# PAGE03_POWER_SUPPLY.net
KiCad netlist of a schematic drawn in Altium Designer
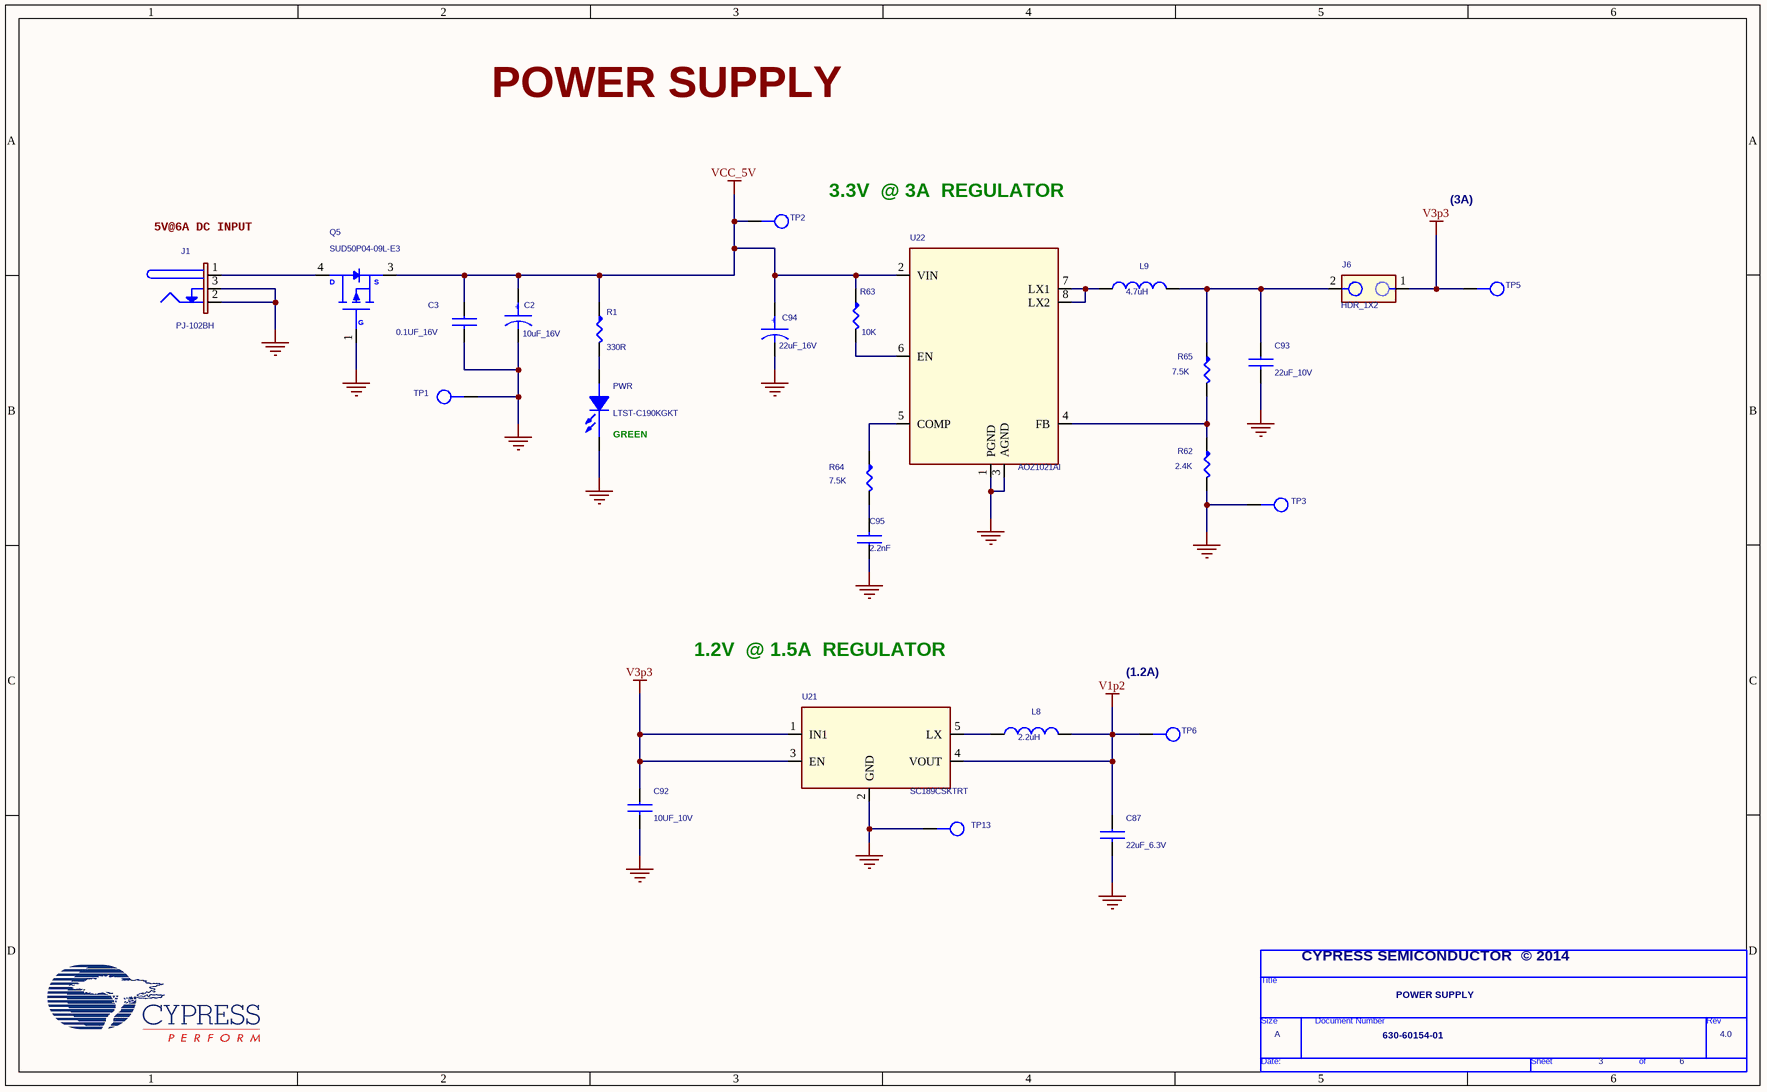
[diagram p0: PAGE03_POWER SUPPLY.SchDoc]

(export (version "E")
  (design (tool "Eeschema 10.0.6"))
  (components
    (comp (ref "*")
      (value "TitleBlock0")
      (fields
        (field (name "PAGE COUNT") "6")
        (field (name "PAGE NUMBER") "3")
        (field (name "PAGE SIZE") "A")
        (field (name "TITLE") "POWER SUPPLY")
        (field (name "REVCODE") "4.0")
        (field (name "DOC") "630-60154-01")
      )
      (libsource (lib "*") (part "TitleBlock0"))
    )
    (comp (ref "C2")
      (value "10uF_16V")
      (description "CAP TANT 10UF 16V 20% 1206")
      (fields (field (name "PART NUMBER") "TAJA106M016RNJ") (field (name "MANUFACTURER") "AVX Corporation"))
      (libsource (lib "*") (part "CAP POL"))
    )
    (comp (ref "C3")
      (value "0.1UF_16V")
      (footprint "CAPC1005X56M")
      (libsource (lib "*") (part "CAPACITOR NON-POL"))
    )
    (comp (ref "C87") (value "22uF_6.3V") (libsource (lib "*") (part "CAPACITOR NON-POL")))
    (comp (ref "C92")
      (value "10UF_10V")
      (footprint "CAPC2012X145M")
      (libsource (lib "*") (part "CAPACITOR NON-POL"))
    )
    (comp (ref "C93") (value "22uF_10V") (libsource (lib "*") (part "CAPACITOR NON-POL")))
    (comp (ref "C94")
      (value "22uF_16V")
      (description "CAP TANT 22UF 16V 10% 1206")
      (fields (field (name "MANUFACTURER") "Nichicon") (field (name "PART NUMBER") "F951C226KQAAQ2"))
      (libsource (lib "*") (part "CAP POL"))
    )
    (comp (ref "C95")
      (value "2.2nF")
      (description "CAP CER 2200PF 50V 10% X7R 0805")
      (fields (field (name "MANUFACTURER") "Yageo") (field (name "PART NUMBER") "CC0805KRX7R9BB222"))
      (libsource (lib "*") (part "CAPACITOR NON-POL"))
    )
    (comp (ref "J1")
      (value "PJ-102BH")
      (description "CONN PWR JACK 2.5X5.5MM HIGH CUR")
      (fields (field (name "MANUFACTURER") "CUI Inc"))
      (libsource (lib "*") (part "PowerJack"))
    )
    (comp (ref "J6")
      (value "HDR_1X2")
      (footprint "SAMTEC_TSW-102-08-G-S")
      (fields (field (name "MANUFACTURER") "Samtec Inc") (field (name "PART NUMBER") "TSW-102-08-G-S"))
      (libsource (lib "*") (part "HEADER_1x2"))
    )
    (comp (ref "L8")
      (value "2.2uH")
      (description "INDUCTOR 2.2UH 1.20A 20% 1210")
      (fields (field (name "PART NUMBER") "NLCV32T-2R2M-PFR") (field (name "MANUFACTURER") "TDK Corporation"))
      (libsource (lib "*") (part "INDUCTOR"))
    )
    (comp (ref "L9")
      (value "4.7uH")
      (description "INDUCTOR 4.7UH 2.7A 20% SMD")
      (fields (field (name "PART NUMBER") "NR6028T4R7M") (field (name "MANUFACTURER") "Taiyo Yuden"))
      (libsource (lib "*") (part "INDUCTOR"))
    )
    (comp (ref "PWR")
      (value "LTST-C190KGKT")
      (description "LED GREEN CLEAR 0603 SMD")
      (fields (field (name "MANUFACTURER") "Lite-On"))
      (libsource (lib "*") (part "LED"))
    )
    (comp (ref "Q5") (value "SUD50P04-09L-E3") (libsource (lib "*") (part "SUD50P04-09L-E3")))
    (comp (ref "R1")
      (value "330R")
      (footprint "RESC1608X55M")
      (description "RES 180 OHM 1/16W 1% 0402 SMD")
      (fields (field (name "MANUFACTURER") "Vishay") (field (name "PART NUMBER") "CRCW0402180RFKED"))
      (libsource (lib "*") (part "R_Dup1"))
    )
    (comp (ref "R62")
      (value "2.4K")
      (footprint "RESC1608X55M")
      (description "RES 2.4K OHM 1/10W 1% 0603 SMD")
      (fields (field (name "MANUFACTURER") "Panasonic - ECG") (field (name "PART NUMBER") "ERJ-3EKF2401V"))
      (libsource (lib "*") (part "R_Dup1"))
    )
    (comp (ref "R63")
      (value "10K")
      (footprint "RESC1608X55M")
      (description "RES 10.0K OHM 1/10W 1% 0603 SMD")
      (fields (field (name "MANUFACTURER") "Panasonic - ECG") (field (name "PART NUMBER") "ERJ-3EKF1002V"))
      (libsource (lib "*") (part "R_Dup1"))
    )
    (comp (ref "R64")
      (value "7.5K")
      (footprint "RESC1608X55M")
      (description "RES 7.5K OHM 1/10W 1% 0603 SMD")
      (fields (field (name "PART NUMBER") "ERJ-3EKF7501V") (field (name "MANUFACTURER") "Panasonic - ECG"))
      (libsource (lib "*") (part "R_Dup1"))
    )
    (comp (ref "R65")
      (value "7.5K")
      (footprint "RESC1608X55M")
      (description "RES 7.5K OHM 1/10W 1% 0603 SMD")
      (fields (field (name "MANUFACTURER") "Panasonic - ECG") (field (name "PART NUMBER") "ERJ-3EKF7501V"))
      (libsource (lib "*") (part "R_Dup1"))
    )
    (comp (ref "TP1")
      (value "TP_BLACK")
      (footprint "KEYSTONE_5000")
      (description "TEST POINT PC MINI .040\"D BLACK")
      (fields (field (name "MANUFACTURER") "Keystone") (field (name "PART_NUMBER") "5000"))
      (libsource (lib "*") (part "TP"))
    )
    (comp (ref "TP2")
      (value "TP_RED")
      (footprint "KEYSTONE_5000")
      (description "TEST POINT PC MINI .040\"D RED")
      (fields (field (name "PART_NUMBER") "5000") (field (name "MANUFACTURER") "Keystone"))
      (libsource (lib "*") (part "TP"))
    )
    (comp (ref "TP3")
      (value "TP_BLACK")
      (footprint "KEYSTONE_5000")
      (description "TEST POINT PC MINI .040\"D BLACK")
      (fields (field (name "PART_NUMBER") "5000") (field (name "MANUFACTURER") "Keystone"))
      (libsource (lib "*") (part "TP"))
    )
    (comp (ref "TP5")
      (value "TP_RED")
      (footprint "KEYSTONE_5000")
      (description "TEST POINT PC MINI .040\"D RED")
      (fields (field (name "PART_NUMBER") "5000") (field (name "MANUFACTURER") "Keystone"))
      (libsource (lib "*") (part "TP"))
    )
    (comp (ref "TP6")
      (value "TP_RED")
      (footprint "KEYSTONE_5000")
      (description "TEST POINT PC MINI .040\"D RED")
      (fields (field (name "MANUFACTURER") "Keystone") (field (name "PART NUMBER") "5000"))
      (libsource (lib "*") (part "TP"))
    )
    (comp (ref "TP13")
      (value "TP_BLACK")
      (footprint "KEYSTONE_5000")
      (description "TEST POINT PC MINI .040\"D BLACK")
      (fields (field (name "PART NUMBER") "5000") (field (name "MANUFACTURER") "Keystone"))
      (libsource (lib "*") (part "TP"))
    )
    (comp (ref "U21")
      (value "SC189CSKTRT")
      (footprint "SOT95P280X145-5M")
      (description "IC REG BUCK SYNC 1.2V SOT23-5")
      (fields (field (name "MANUFACTURER") "Semtech"))
      (libsource (lib "*") (part "SC189CSKTRT"))
    )
    (comp (ref "U22")
      (value "AOZ1021AI")
      (footprint "SOIC127P600X175-8M")
      (description "IC REG BUCK SYNC ADJ 3A 8SOIC")
      (fields (field (name "MANUFACTURER") "Alpha & Omega Semiconductor Inc"))
      (libsource (lib "*") (part "AOZ1021AI"))
    )
  )
  (nets
    (net (code "1") (name "GND") (class "Default")
      (node (ref "C2") (pin "2") (pinfunction "2_2") (pintype "passive"))
      (node (ref "C3") (pin "2") (pinfunction "2_2") (pintype "passive"))
      (node (ref "C87") (pin "2") (pinfunction "2_2") (pintype "passive"))
      (node (ref "C92") (pin "2") (pinfunction "2_2") (pintype "passive"))
      (node (ref "C93") (pin "2") (pinfunction "2_2") (pintype "passive"))
      (node (ref "C94") (pin "2") (pinfunction "2_2") (pintype "passive"))
      (node (ref "C95") (pin "1") (pinfunction "1_1") (pintype "passive"))
      (node (ref "J1") (pin "2") (pinfunction "2_2") (pintype "passive"))
      (node (ref "J1") (pin "3") (pinfunction "3_3") (pintype "passive"))
      (node (ref "PWR") (pin "2") (pinfunction "CATHODE_2") (pintype "passive"))
      (node (ref "Q5") (pin "1") (pinfunction "G_1") (pintype "passive"))
      (node (ref "R62") (pin "2") (pinfunction "2_2") (pintype "passive"))
      (node (ref "TP1") (pin "1") (pinfunction "TP_1") (pintype "passive"))
      (node (ref "TP13") (pin "1") (pinfunction "TP_1") (pintype "passive"))
      (node (ref "TP3") (pin "1") (pinfunction "TP_1") (pintype "passive"))
      (node (ref "U21") (pin "2") (pinfunction "GND_2") (pintype "passive"))
      (node (ref "U22") (pin "1") (pinfunction "PGND_1") (pintype "passive"))
      (node (ref "U22") (pin "3") (pinfunction "AGND_3") (pintype "passive"))
    )
    (net (code "2") (name "Net-(C93-Pad1)") (class "Default")
      (node (ref "C93") (pin "1") (pinfunction "1_1") (pintype "passive"))
      (node (ref "J6") (pin "2") (pinfunction "2_2") (pintype "passive"))
      (node (ref "L9") (pin "2") (pinfunction "2_2") (pintype "passive"))
      (node (ref "R65") (pin "1") (pinfunction "1_1") (pintype "passive"))
    )
    (net (code "3") (name "Net-(C95-Pad2)") (class "Default")
      (node (ref "C95") (pin "2") (pinfunction "2_2") (pintype "passive"))
      (node (ref "R64") (pin "2") (pinfunction "2_2") (pintype "passive"))
    )
    (net (code "4") (name "Net-(PWR-ANODE)") (class "Default")
      (node (ref "PWR") (pin "1") (pinfunction "ANODE_1") (pintype "passive"))
      (node (ref "R1") (pin "2") (pinfunction "2_2") (pintype "passive"))
    )
    (net (code "5") (name "Net-(Q5-D)") (class "Default")
      (node (ref "J1") (pin "1") (pinfunction "1_1") (pintype "passive"))
      (node (ref "Q5") (pin "4") (pinfunction "D_4") (pintype "passive"))
    )
    (net (code "6") (name "Net-(U21-LX)") (class "Default")
      (node (ref "L8") (pin "1") (pinfunction "1_1") (pintype "passive"))
      (node (ref "U21") (pin "5") (pinfunction "LX_5") (pintype "passive"))
    )
    (net (code "7") (name "Net-(U22-COMP)") (class "Default")
      (node (ref "R64") (pin "1") (pinfunction "1_1") (pintype "passive"))
      (node (ref "U22") (pin "5") (pinfunction "COMP_5") (pintype "passive"))
    )
    (net (code "8") (name "Net-(U22-EN)") (class "Default")
      (node (ref "R63") (pin "2") (pinfunction "2_2") (pintype "passive"))
      (node (ref "U22") (pin "6") (pinfunction "EN_6") (pintype "passive"))
    )
    (net (code "9") (name "Net-(U22-FB)") (class "Default")
      (node (ref "R62") (pin "1") (pinfunction "1_1") (pintype "passive"))
      (node (ref "R65") (pin "2") (pinfunction "2_2") (pintype "passive"))
      (node (ref "U22") (pin "4") (pinfunction "FB_4") (pintype "passive"))
    )
    (net (code "10") (name "Net-(U22-LX1)") (class "Default")
      (node (ref "L9") (pin "1") (pinfunction "1_1") (pintype "passive"))
      (node (ref "U22") (pin "7") (pinfunction "LX1_7") (pintype "passive"))
      (node (ref "U22") (pin "8") (pinfunction "LX2_8") (pintype "passive"))
    )
    (net (code "11") (name "V1p2") (class "Default")
      (node (ref "C87") (pin "1") (pinfunction "1_1") (pintype "passive"))
      (node (ref "L8") (pin "2") (pinfunction "2_2") (pintype "passive"))
      (node (ref "TP6") (pin "1") (pinfunction "TP_1") (pintype "passive"))
      (node (ref "U21") (pin "4") (pinfunction "VOUT_4") (pintype "passive"))
    )
    (net (code "12") (name "V3p3") (class "Default")
      (node (ref "C92") (pin "1") (pinfunction "1_1") (pintype "passive"))
      (node (ref "J6") (pin "1") (pinfunction "1_1") (pintype "passive"))
      (node (ref "TP5") (pin "1") (pinfunction "TP_1") (pintype "passive"))
      (node (ref "U21") (pin "1") (pinfunction "IN1_1") (pintype "passive"))
      (node (ref "U21") (pin "3") (pinfunction "EN_3") (pintype "passive"))
    )
    (net (code "13") (name "VCC_5V") (class "Default")
      (node (ref "C2") (pin "1") (pinfunction "1_1") (pintype "passive"))
      (node (ref "C3") (pin "1") (pinfunction "1_1") (pintype "passive"))
      (node (ref "C94") (pin "1") (pinfunction "1_1") (pintype "passive"))
      (node (ref "Q5") (pin "3") (pinfunction "S_3") (pintype "passive"))
      (node (ref "R1") (pin "1") (pinfunction "1_1") (pintype "passive"))
      (node (ref "R63") (pin "1") (pinfunction "1_1") (pintype "passive"))
      (node (ref "TP2") (pin "1") (pinfunction "TP_1") (pintype "passive"))
      (node (ref "U22") (pin "2") (pinfunction "VIN_2") (pintype "passive"))
    )
  )
)
